# arduino_shield_drumline.net
KiCad netlist of a schematic drawn in EAGLE
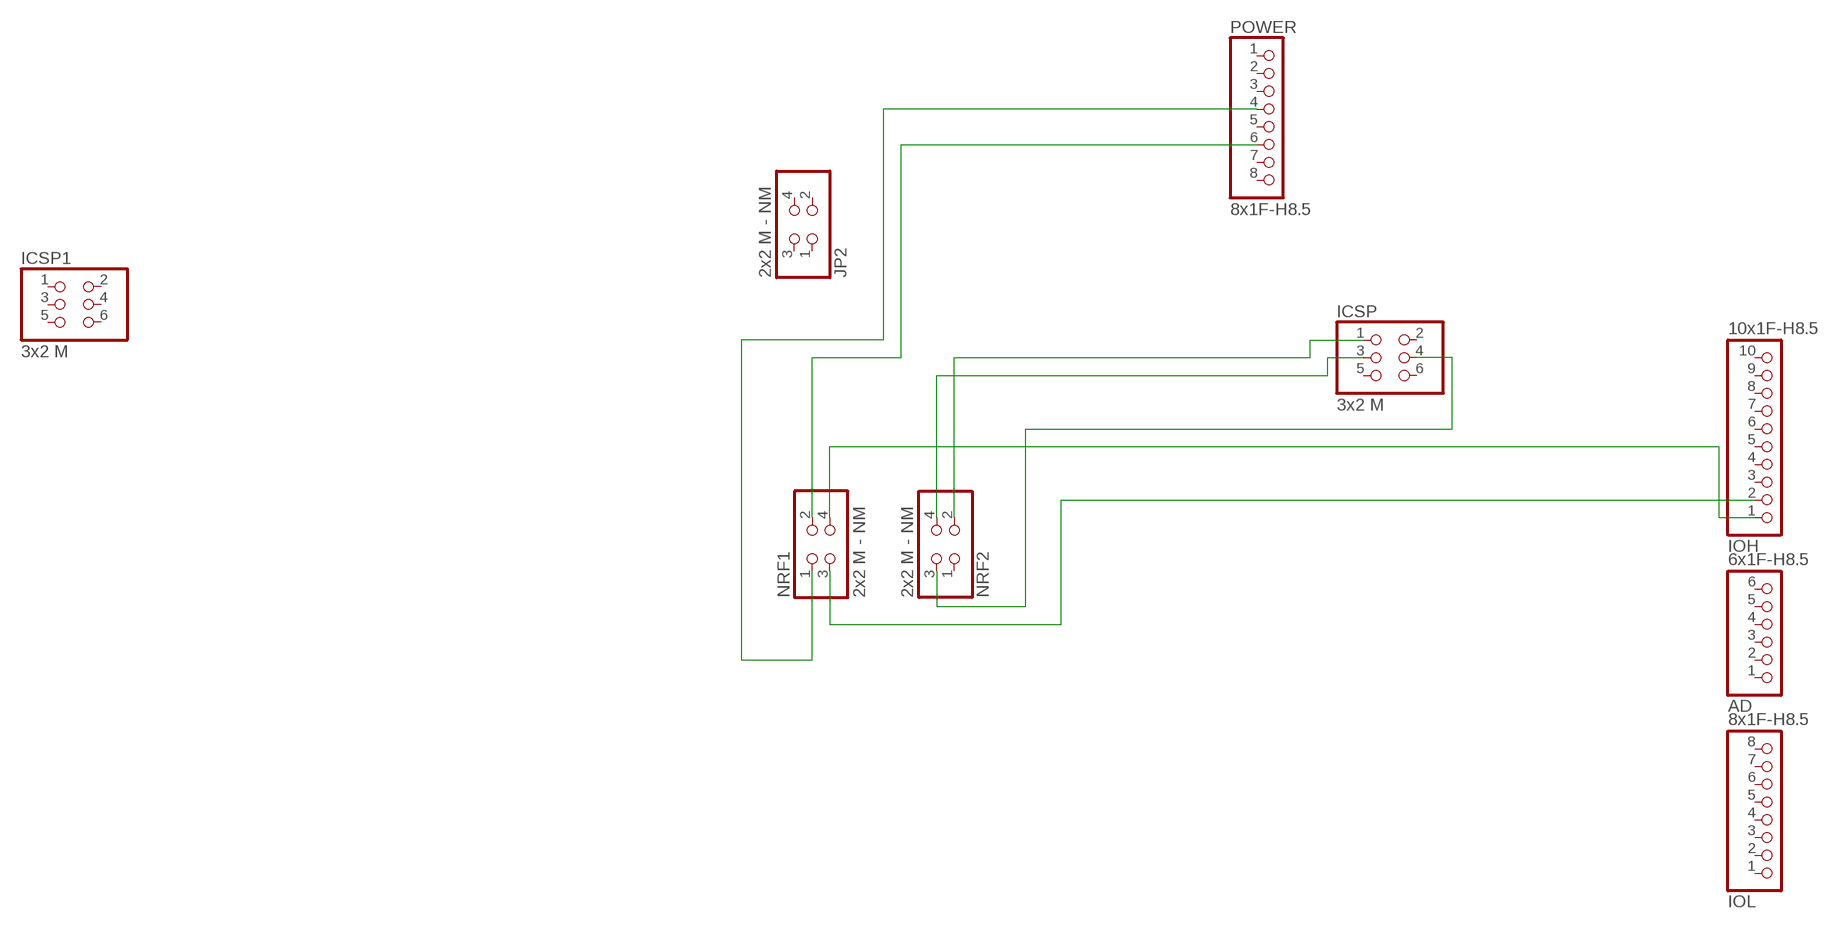
[diagram p0: schematic, sheet 1]

(export (version "E")
  (design (tool "Eeschema 10.0.6"))
  (components
    (comp (ref "AD")
      (value "6x1F-H8.5")
      (footprint "eagle-import:1X06")
      (libsource (lib "eagle-import") (part "PINHD-1X6"))
    )
    (comp (ref "ICSP")
      (value "3x2 M")
      (footprint "eagle-import:2X03")
      (libsource (lib "eagle-import") (part "PINHD-2X3"))
    )
    (comp (ref "ICSP1")
      (value "3x2 M")
      (footprint "eagle-import:2X03")
      (libsource (lib "eagle-import") (part "PINHD-2X3"))
    )
    (comp (ref "IOH")
      (value "10x1F-H8.5")
      (footprint "eagle-import:1X10")
      (libsource (lib "eagle-import") (part "PINHD-1X10_ARD"))
    )
    (comp (ref "IOL")
      (value "8x1F-H8.5")
      (footprint "eagle-import:1X08")
      (libsource (lib "eagle-import") (part "PINHD-1X8"))
    )
    (comp (ref "JP2")
      (value "2x2 M - NM")
      (footprint "eagle-import:2X02")
      (libsource (lib "eagle-import") (part "PINHD-2X2"))
    )
    (comp (ref "NRF1")
      (value "2x2 M - NM")
      (footprint "eagle-import:2X02")
      (libsource (lib "eagle-import") (part "PINHD-2X2"))
    )
    (comp (ref "NRF2")
      (value "2x2 M - NM")
      (footprint "eagle-import:2X02")
      (libsource (lib "eagle-import") (part "PINHD-2X2"))
    )
    (comp (ref "POWER")
      (value "8x1F-H8.5")
      (footprint "eagle-import:1X08")
      (libsource (lib "eagle-import") (part "PINHD-1X8"))
    )
  )
  (nets
    (net (code "1") (name "Net-(ICSP-Pad1)") (class "Default")
      (node (ref "ICSP") (pin "1") (pinfunction "1_1") (pintype "passive"))
      (node (ref "NRF2") (pin "2") (pinfunction "2_2") (pintype "passive"))
    )
    (net (code "2") (name "Net-(ICSP-Pad3)") (class "Default")
      (node (ref "ICSP") (pin "3") (pinfunction "3_3") (pintype "passive"))
      (node (ref "NRF2") (pin "4") (pinfunction "4_4") (pintype "passive"))
    )
    (net (code "3") (name "Net-(ICSP-Pad4)") (class "Default")
      (node (ref "ICSP") (pin "4") (pinfunction "4_4") (pintype "passive"))
      (node (ref "NRF2") (pin "3") (pinfunction "3_3") (pintype "passive"))
    )
    (net (code "4") (name "Net-(IOH-Pad1)") (class "Default")
      (node (ref "IOH") (pin "1") (pinfunction "1_1") (pintype "passive"))
      (node (ref "NRF1") (pin "4") (pinfunction "4_4") (pintype "passive"))
    )
    (net (code "5") (name "Net-(IOH-Pad2)") (class "Default")
      (node (ref "IOH") (pin "2") (pinfunction "2_2") (pintype "passive"))
      (node (ref "NRF1") (pin "3") (pinfunction "3_3") (pintype "passive"))
    )
    (net (code "6") (name "Net-(NRF1-Pad1)") (class "Default")
      (node (ref "NRF1") (pin "1") (pinfunction "1_1") (pintype "passive"))
      (node (ref "POWER") (pin "4") (pinfunction "4_4") (pintype "passive"))
    )
    (net (code "7") (name "Net-(NRF1-Pad2)") (class "Default")
      (node (ref "NRF1") (pin "2") (pinfunction "2_2") (pintype "passive"))
      (node (ref "POWER") (pin "6") (pinfunction "6_6") (pintype "passive"))
    )
    (net (code "8") (name "unconnected-(AD-Pad1)") (class "Default")
      (node (ref "AD") (pin "1") (pinfunction "1_1") (pintype "passive"))
    )
    (net (code "9") (name "unconnected-(AD-Pad2)") (class "Default")
      (node (ref "AD") (pin "2") (pinfunction "2_2") (pintype "passive"))
    )
    (net (code "10") (name "unconnected-(AD-Pad3)") (class "Default")
      (node (ref "AD") (pin "3") (pinfunction "3_3") (pintype "passive"))
    )
    (net (code "11") (name "unconnected-(AD-Pad4)") (class "Default")
      (node (ref "AD") (pin "4") (pinfunction "4_4") (pintype "passive"))
    )
    (net (code "12") (name "unconnected-(AD-Pad5)") (class "Default")
      (node (ref "AD") (pin "5") (pinfunction "5_5") (pintype "passive"))
    )
    (net (code "13") (name "unconnected-(AD-Pad6)") (class "Default")
      (node (ref "AD") (pin "6") (pinfunction "6_6") (pintype "passive"))
    )
    (net (code "14") (name "unconnected-(ICSP-Pad2)") (class "Default")
      (node (ref "ICSP") (pin "2") (pinfunction "2_2") (pintype "passive"))
    )
    (net (code "15") (name "unconnected-(ICSP-Pad5)") (class "Default")
      (node (ref "ICSP") (pin "5") (pinfunction "5_5") (pintype "passive"))
    )
    (net (code "16") (name "unconnected-(ICSP-Pad6)") (class "Default")
      (node (ref "ICSP") (pin "6") (pinfunction "6_6") (pintype "passive"))
    )
    (net (code "17") (name "unconnected-(ICSP1-Pad1)") (class "Default")
      (node (ref "ICSP1") (pin "1") (pinfunction "1_1") (pintype "passive"))
    )
    (net (code "18") (name "unconnected-(ICSP1-Pad2)") (class "Default")
      (node (ref "ICSP1") (pin "2") (pinfunction "2_2") (pintype "passive"))
    )
    (net (code "19") (name "unconnected-(ICSP1-Pad3)") (class "Default")
      (node (ref "ICSP1") (pin "3") (pinfunction "3_3") (pintype "passive"))
    )
    (net (code "20") (name "unconnected-(ICSP1-Pad4)") (class "Default")
      (node (ref "ICSP1") (pin "4") (pinfunction "4_4") (pintype "passive"))
    )
    (net (code "21") (name "unconnected-(ICSP1-Pad5)") (class "Default")
      (node (ref "ICSP1") (pin "5") (pinfunction "5_5") (pintype "passive"))
    )
    (net (code "22") (name "unconnected-(ICSP1-Pad6)") (class "Default")
      (node (ref "ICSP1") (pin "6") (pinfunction "6_6") (pintype "passive"))
    )
    (net (code "23") (name "unconnected-(IOH-Pad3)") (class "Default")
      (node (ref "IOH") (pin "3") (pinfunction "3_3") (pintype "passive"))
    )
    (net (code "24") (name "unconnected-(IOH-Pad4)") (class "Default")
      (node (ref "IOH") (pin "4") (pinfunction "4_4") (pintype "passive"))
    )
    (net (code "25") (name "unconnected-(IOH-Pad5)") (class "Default")
      (node (ref "IOH") (pin "5") (pinfunction "5_5") (pintype "passive"))
    )
    (net (code "26") (name "unconnected-(IOH-Pad6)") (class "Default")
      (node (ref "IOH") (pin "6") (pinfunction "6_6") (pintype "passive"))
    )
    (net (code "27") (name "unconnected-(IOH-Pad7)") (class "Default")
      (node (ref "IOH") (pin "7") (pinfunction "7_7") (pintype "passive"))
    )
    (net (code "28") (name "unconnected-(IOH-Pad8)") (class "Default")
      (node (ref "IOH") (pin "8") (pinfunction "8_8") (pintype "passive"))
    )
    (net (code "29") (name "unconnected-(IOH-Pad9)") (class "Default")
      (node (ref "IOH") (pin "9") (pinfunction "9_9") (pintype "passive"))
    )
    (net (code "30") (name "unconnected-(IOH-Pad10)") (class "Default")
      (node (ref "IOH") (pin "10") (pinfunction "10_10") (pintype "passive"))
    )
    (net (code "31") (name "unconnected-(IOL-Pad1)") (class "Default")
      (node (ref "IOL") (pin "1") (pinfunction "1_1") (pintype "passive"))
    )
    (net (code "32") (name "unconnected-(IOL-Pad2)") (class "Default")
      (node (ref "IOL") (pin "2") (pinfunction "2_2") (pintype "passive"))
    )
    (net (code "33") (name "unconnected-(IOL-Pad3)") (class "Default")
      (node (ref "IOL") (pin "3") (pinfunction "3_3") (pintype "passive"))
    )
    (net (code "34") (name "unconnected-(IOL-Pad4)") (class "Default")
      (node (ref "IOL") (pin "4") (pinfunction "4_4") (pintype "passive"))
    )
    (net (code "35") (name "unconnected-(IOL-Pad5)") (class "Default")
      (node (ref "IOL") (pin "5") (pinfunction "5_5") (pintype "passive"))
    )
    (net (code "36") (name "unconnected-(IOL-Pad6)") (class "Default")
      (node (ref "IOL") (pin "6") (pinfunction "6_6") (pintype "passive"))
    )
    (net (code "37") (name "unconnected-(IOL-Pad7)") (class "Default")
      (node (ref "IOL") (pin "7") (pinfunction "7_7") (pintype "passive"))
    )
    (net (code "38") (name "unconnected-(IOL-Pad8)") (class "Default")
      (node (ref "IOL") (pin "8") (pinfunction "8_8") (pintype "passive"))
    )
    (net (code "39") (name "unconnected-(JP2-Pad1)") (class "Default")
      (node (ref "JP2") (pin "1") (pinfunction "1_1") (pintype "passive"))
    )
    (net (code "40") (name "unconnected-(JP2-Pad2)") (class "Default")
      (node (ref "JP2") (pin "2") (pinfunction "2_2") (pintype "passive"))
    )
    (net (code "41") (name "unconnected-(JP2-Pad3)") (class "Default")
      (node (ref "JP2") (pin "3") (pinfunction "3_3") (pintype "passive"))
    )
    (net (code "42") (name "unconnected-(JP2-Pad4)") (class "Default")
      (node (ref "JP2") (pin "4") (pinfunction "4_4") (pintype "passive"))
    )
    (net (code "43") (name "unconnected-(NRF2-Pad1)") (class "Default")
      (node (ref "NRF2") (pin "1") (pinfunction "1_1") (pintype "passive"))
    )
    (net (code "44") (name "unconnected-(POWER-Pad1)") (class "Default")
      (node (ref "POWER") (pin "1") (pinfunction "1_1") (pintype "passive"))
    )
    (net (code "45") (name "unconnected-(POWER-Pad2)") (class "Default")
      (node (ref "POWER") (pin "2") (pinfunction "2_2") (pintype "passive"))
    )
    (net (code "46") (name "unconnected-(POWER-Pad3)") (class "Default")
      (node (ref "POWER") (pin "3") (pinfunction "3_3") (pintype "passive"))
    )
    (net (code "47") (name "unconnected-(POWER-Pad5)") (class "Default")
      (node (ref "POWER") (pin "5") (pinfunction "5_5") (pintype "passive"))
    )
    (net (code "48") (name "unconnected-(POWER-Pad7)") (class "Default")
      (node (ref "POWER") (pin "7") (pinfunction "7_7") (pintype "passive"))
    )
    (net (code "49") (name "unconnected-(POWER-Pad8)") (class "Default")
      (node (ref "POWER") (pin "8") (pinfunction "8_8") (pintype "passive"))
    )
  )
)
